# STM32-ROMI_Rev_A_4_3V_5V.net
KiCad netlist of a schematic drawn in Altium Designer
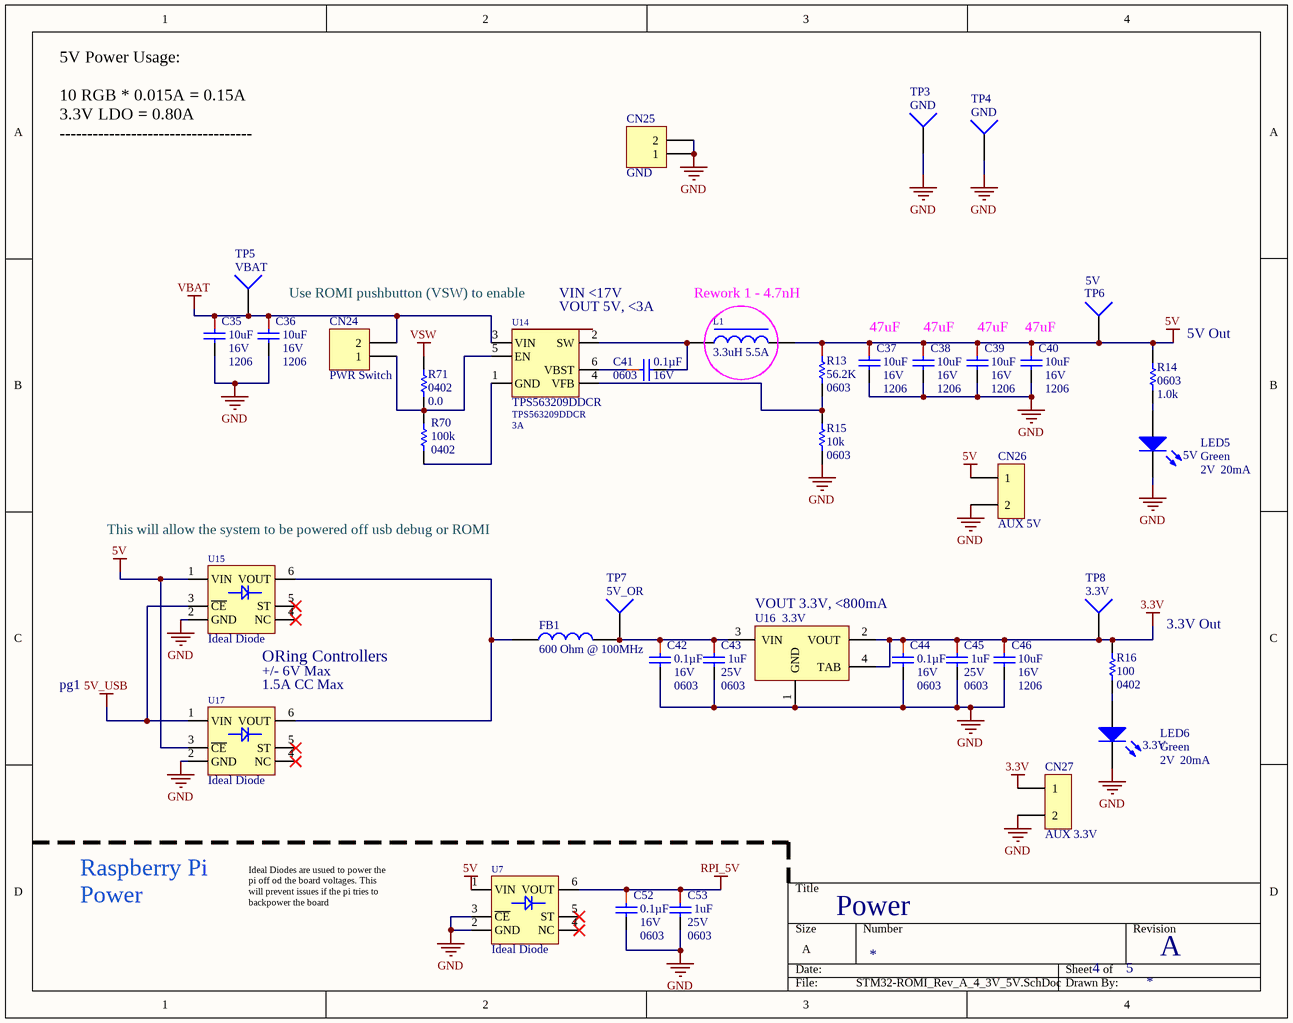
[diagram p0: STM32-ROMI_Rev_A_4_3V_5V.SchDoc]

(export (version "E")
  (design (tool "Eeschema 10.0.6"))
  (components
    (comp (ref "C35")
      (value "10uF")
      (footprint "CAPC1206(3216)_M")
      (fields (field (name "VOLTAGE - RATED") "16V") (field (name "PACKAGE") "1206"))
      (libsource (lib "Kyle-Passive") (part "CAP CER 10UF 16V 1206"))
    )
    (comp (ref "C36")
      (value "10uF")
      (footprint "CAPC1206(3216)_M")
      (fields (field (name "VOLTAGE - RATED") "16V") (field (name "PACKAGE") "1206"))
      (libsource (lib "Kyle-Passive") (part "CAP CER 10UF 16V 1206"))
    )
    (comp (ref "C37")
      (value "10uF")
      (footprint "CAPC1206(3216)_M")
      (fields (field (name "VOLTAGE - RATED") "16V") (field (name "PACKAGE") "1206"))
      (libsource (lib "Kyle-Passive") (part "CAP CER 10UF 16V 1206"))
    )
    (comp (ref "C38")
      (value "10uF")
      (footprint "CAPC1206(3216)_M")
      (fields (field (name "VOLTAGE - RATED") "16V") (field (name "PACKAGE") "1206"))
      (libsource (lib "Kyle-Passive") (part "CAP CER 10UF 16V 1206"))
    )
    (comp (ref "C39")
      (value "10uF")
      (footprint "CAPC1206(3216)_M")
      (fields (field (name "VOLTAGE - RATED") "16V") (field (name "PACKAGE") "1206"))
      (libsource (lib "Kyle-Passive") (part "CAP CER 10UF 16V 1206"))
    )
    (comp (ref "C40")
      (value "10uF")
      (footprint "CAPC1206(3216)_M")
      (fields (field (name "VOLTAGE - RATED") "16V") (field (name "PACKAGE") "1206"))
      (libsource (lib "Kyle-Passive") (part "CAP CER 10UF 16V 1206"))
    )
    (comp (ref "C41")
      (value "0.1uF")
      (footprint "CAPC0603(1608)_L")
      (description "0.1uF 0603 16V")
      (fields
        (field (name "MANUFACTURER") "Kemet")
        (field (name "MANUFACTURER PART NUMBER") "C0603C104K4RACTU")
        (field (name "CAPACITANCE") "0.1µF")
        (field (name "PACKAGE / CASE") "0603")
        (field (name "VOLTAGE - RATED") "16V")
      )
      (libsource (lib "Kyle-Passive") (part "CAP CER 0.1UF 16V 10% X7R 0603"))
    )
    (comp (ref "C42")
      (value "0.1uF")
      (footprint "CAPC0603(1608)_L")
      (description "0.1uF 0603 16V")
      (fields
        (field (name "MANUFACTURER") "Kemet")
        (field (name "MANUFACTURER PART NUMBER") "C0603C104K4RACTU")
        (field (name "CAPACITANCE") "0.1µF")
        (field (name "PACKAGE / CASE") "0603")
        (field (name "VOLTAGE - RATED") "16V")
      )
      (libsource (lib "Kyle-Passive") (part "CAP CER 0.1UF 16V 10% X7R 0603"))
    )
    (comp (ref "C43")
      (value "1uF")
      (footprint "CAPC0603(1608)_N")
      (description "1uF 0603 25V")
      (fields
        (field (name "MANUFACTURER") "TDK Corporation")
        (field (name "MANUFACTURER PART NUMBER") "CGA3E1X7R1E105K080AC")
        (field (name "VOLTAGE - RATED") "25V")
        (field (name "PACKAGE / CASE") "0603")
      )
      (libsource (lib "OLogic-Passive") (part "CAP CER 1UF 25V 10% X7R 0603"))
    )
    (comp (ref "C44")
      (value "0.1uF")
      (footprint "CAPC0603(1608)_L")
      (description "0.1uF 0603 16V")
      (fields
        (field (name "MANUFACTURER") "Kemet")
        (field (name "MANUFACTURER PART NUMBER") "C0603C104K4RACTU")
        (field (name "CAPACITANCE") "0.1µF")
        (field (name "PACKAGE / CASE") "0603")
        (field (name "VOLTAGE - RATED") "16V")
      )
      (libsource (lib "Kyle-Passive") (part "CAP CER 0.1UF 16V 10% X7R 0603"))
    )
    (comp (ref "C45")
      (value "1uF")
      (footprint "CAPC0603(1608)_N")
      (description "1uF 0603 25V")
      (fields
        (field (name "MANUFACTURER") "TDK Corporation")
        (field (name "MANUFACTURER PART NUMBER") "CGA3E1X7R1E105K080AC")
        (field (name "VOLTAGE - RATED") "25V")
        (field (name "PACKAGE / CASE") "0603")
      )
      (libsource (lib "OLogic-Passive") (part "CAP CER 1UF 25V 10% X7R 0603"))
    )
    (comp (ref "C46")
      (value "10uF")
      (footprint "CAPC1206(3216)_M")
      (fields (field (name "VOLTAGE - RATED") "16V") (field (name "PACKAGE") "1206"))
      (libsource (lib "Kyle-Passive") (part "CAP CER 10UF 16V 1206"))
    )
    (comp (ref "C52")
      (value "0.1uF")
      (footprint "CAPC0603(1608)_L")
      (description "0.1uF 0603 16V")
      (fields
        (field (name "MANUFACTURER") "Kemet")
        (field (name "MANUFACTURER PART NUMBER") "C0603C104K4RACTU")
        (field (name "CAPACITANCE") "0.1µF")
        (field (name "PACKAGE / CASE") "0603")
        (field (name "VOLTAGE - RATED") "16V")
      )
      (libsource (lib "Kyle-Passive") (part "CAP CER 0.1UF 16V 10% X7R 0603"))
    )
    (comp (ref "C53")
      (value "1uF")
      (footprint "CAPC0603(1608)_N")
      (description "1uF 0603 25V")
      (fields
        (field (name "MANUFACTURER") "TDK Corporation")
        (field (name "MANUFACTURER PART NUMBER") "CGA3E1X7R1E105K080AC")
        (field (name "VOLTAGE - RATED") "25V")
        (field (name "PACKAGE / CASE") "0603")
      )
      (libsource (lib "OLogic-Passive") (part "CAP CER 1UF 25V 10% X7R 0603"))
    )
    (comp (ref "CN24")
      (value "PWR Switch")
      (footprint "HDR1X2")
      (description "Header, 2-Pin")
      (fields
        (field (name "MANUFACTURER") "Sullins Connector Solutions")
        (field (name "MANUFACTURER PART NUMBER") "PRPC002SAAN-RC")
      )
      (libsource (lib "OLogic-Connectors") (part "Header 2"))
    )
    (comp (ref "CN25")
      (value "GND")
      (footprint "HDR1X2")
      (description "Header, 2-Pin")
      (fields
        (field (name "MANUFACTURER") "Sullins Connector Solutions")
        (field (name "MANUFACTURER PART NUMBER") "PRPC002SAAN-RC")
      )
      (libsource (lib "OLogic-Connectors") (part "Header 2"))
    )
    (comp (ref "CN26")
      (value "AUX 5V")
      (footprint "Molex 1x2 Microfit 3.0")
      (description "Molex Microfit 1x2 Vert Header")
      (fields
        (field (name "MANUFACTURER") "Molex, LLC")
        (field (name "MANUFACTURER PART NUMBER") "0430450227")
      )
      (libsource (lib "OLogic-Connectors") (part "MICROFIT 3.0 HDR VERT CPI 2CKT"))
    )
    (comp (ref "CN27")
      (value "AUX 3.3V")
      (footprint "Molex 1x2 Microfit 3.0")
      (description "Molex Microfit 1x2 Vert Header")
      (fields
        (field (name "MANUFACTURER") "Molex, LLC")
        (field (name "MANUFACTURER PART NUMBER") "0430450227")
      )
      (libsource (lib "OLogic-Connectors") (part "MICROFIT 3.0 HDR VERT CPI 2CKT"))
    )
    (comp (ref "FB1")
      (value "600 Ohm @ 100MHz")
      (footprint "RESC0805(2012)_N")
      (description "600 OHM 0805 2.0A")
      (fields
        (field (name "MANUFACTURER") "Wurth Electronics Inc")
        (field (name "MANUFACTURER PART NUMBER") "742792040")
        (field (name "CREATOR") "osman")
      )
      (libsource (lib "OLogic-Passive") (part "FERRITE 600 OHM 2.0A 0805"))
    )
    (comp (ref "L1")
      (value "3.3uH 5.5A")
      (footprint "YSPI0530-3R3M")
      (description "Power Inductors 3.3uH ±20% 5.5A SMD,5.2x4.7x3mm RoHS")
      (fields (field (name "MANUFACTURER PART") "YSPI0530-3R3M"))
      (libsource (lib "Kyle-Passive") (part "FIXED IND 3.3UH 5.5A 28 MOHM SMD"))
    )
    (comp (ref "LED5")
      (value "5V")
      (footprint "SM-LED-0603")
      (description "LED GREEN CLEAR THIN 0603 SMD")
      (fields
        (field (name "MANUFACTURER") "Lite-On Inc")
        (field (name "MANUFACTURER PART NUMBER") "LTST-C191KGKT")
        (field (name "COLOR") "Green")
        (field (name "VOLTAGE - FORWARD (VF) (TYP)") "2V")
        (field (name "CURRENT - TEST") "20mA")
      )
      (libsource (lib "Kyle-Diode-Opto-LED") (part "LTST-C191KGKT"))
    )
    (comp (ref "LED6")
      (value "3.3V")
      (footprint "SM-LED-0603")
      (description "LED GREEN CLEAR THIN 0603 SMD")
      (fields
        (field (name "MANUFACTURER") "Lite-On Inc")
        (field (name "MANUFACTURER PART NUMBER") "LTST-C191KGKT")
        (field (name "COLOR") "Green")
        (field (name "VOLTAGE - FORWARD (VF) (TYP)") "2V")
        (field (name "CURRENT - TEST") "20mA")
      )
      (libsource (lib "Kyle-Diode-Opto-LED") (part "LTST-C191KGKT"))
    )
    (comp (ref "R13")
      (value "56.2K")
      (footprint "RESC0603(1608)_L")
      (description "RES SMD 56.2K OHM 1% 1/10W 0603")
      (fields (field (name "PACKAGE / CASE") "0603"))
      (libsource (lib "Kyle-Passive") (part "RES SMD 56.2K OHM 1% 1/10W 0603"))
    )
    (comp (ref "R14")
      (value "1.0K")
      (footprint "RESC0603(1608)_N")
      (description "1.0K 0603")
      (fields
        (field (name "MANUFACTURER") "Stackpole Electronics Inc.")
        (field (name "MANUFACTURER PART NUMBER") "RMCF0603FT1K00")
        (field (name "PACKAGE / CASE") "0603")
        (field (name "RESISTANCE (OHMS)") "1.0k")
      )
      (libsource (lib "Kyle-Passive") (part "RES 1K OHM 1% 1/10W 0603"))
    )
    (comp (ref "R15")
      (value "10K 1%")
      (footprint "RESC0603(1608)_L")
      (description "10K 0603")
      (fields
        (field (name "MANUFACTURER") "Panasonic Electronic Components")
        (field (name "MANUFACTURER PART NUMBER") "ERJ-3EKF1002V")
        (field (name "RESISTANCE (OHMS)") "10k")
        (field (name "PACKAGE / CASE") "0603")
      )
      (libsource (lib "Kyle-Passive") (part "RES 10K OHM 1/10W 1% 0603 SMD"))
    )
    (comp (ref "R16")
      (value "100")
      (footprint "RESC0402(1005)_N")
      (description "100 0402")
      (fields
        (field (name "MANUFACTURER") "Yageo")
        (field (name "MANUFACTURER PART NUMBER") "RC0402FR-07100RL")
        (field (name "SUPPLIER DEVICE PACKAGE") "0402")
      )
      (libsource (lib "OLogic-Passive") (part "RES 100 OHM 1% 1/16W 0402"))
    )
    (comp (ref "R70")
      (value "100K 0402")
      (footprint "RESC0402(1005)_L")
      (fields
        (field (name "MANUFACTURER") "Yageo")
        (field (name "MANUFACTURER PART NUMBER") "RC0402FR-07100KL")
        (field (name "TOLERANCE") "±1%")
        (field (name "SUPPLIER DEVICE PACKAGE") "0402")
        (field (name "RESISTANCE (OHMS)") "100k")
      )
      (libsource (lib "OLogic-Passive") (part "RES 100K OHM 1% 1/16W 0402"))
    )
    (comp (ref "R71")
      (value "0")
      (footprint "RESC0402(1005)_L")
      (description "0.0 0402")
      (fields
        (field (name "MANUFACTURER") "Panasonic Electronic Components")
        (field (name "MANUFACTURER PART NUMBER") "ERJ-2GE0R00X")
        (field (name "SUPPLIER DEVICE PACKAGE") "0402")
        (field (name "RESISTANCE (OHMS)") "0.0")
        (field (name "CREATOR") "osman")
      )
      (libsource (lib "OLogic-Passive") (part "RES 0.0 OHM JUMPER 1/10W 0402"))
    )
    (comp (ref "TP3")
      (value "GND")
      (footprint "TestPoint-SM")
      (description "Test Point")
      (libsource (lib "OLogic-Misc") (part "TestPoint"))
    )
    (comp (ref "TP4")
      (value "GND")
      (footprint "TestPoint-SM")
      (description "Test Point")
      (libsource (lib "OLogic-Misc") (part "TestPoint"))
    )
    (comp (ref "TP5")
      (value "VBAT")
      (footprint "TestPoint-SM")
      (description "Test Point")
      (libsource (lib "OLogic-Misc") (part "TestPoint"))
    )
    (comp (ref "TP6")
      (value "5V")
      (footprint "TestPoint-SM")
      (description "Test Point")
      (libsource (lib "OLogic-Misc") (part "TestPoint"))
    )
    (comp (ref "TP7")
      (value "5V_OR")
      (footprint "TestPoint-SM")
      (description "Test Point")
      (libsource (lib "OLogic-Misc") (part "TestPoint"))
    )
    (comp (ref "TP8")
      (value "3.3V")
      (footprint "TestPoint-SM")
      (description "Test Point")
      (libsource (lib "OLogic-Misc") (part "TestPoint"))
    )
    (comp (ref "U7")
      (value "Ideal Diode")
      (footprint "SC-70-6")
      (description "OR Controller P-Channel 1.5A CC")
      (libsource (lib "Kyle-Reg-Convert") (part "LM66100DCKT"))
    )
    (comp (ref "U14")
      (value "TPS563209DDCR")
      (footprint "SOT23-6")
      (description "IC REG BUCK ADJ 3A TSOT23-6")
      (fields
        (field (name "MANUFACTURER PART NUMBER") "TPS563209DDCR")
        (field (name "CURRENT - OUTPUT") "3A")
      )
      (libsource (lib "Kyle-Reg-Convert") (part "TPS563209DDCR"))
    )
    (comp (ref "U15")
      (value "Ideal Diode")
      (footprint "SC-70-6")
      (description "OR Controller P-Channel 1.5A CC")
      (libsource (lib "Kyle-Reg-Convert") (part "LM66100DCKT"))
    )
    (comp (ref "U16")
      (value "3.3V")
      (footprint "DSO-G3")
      (description "3.3 volt fixed regulator, 800mA")
      (libsource (lib "OLogic-Reg-Convert") (part "LD1117S33"))
    )
    (comp (ref "U17")
      (value "Ideal Diode")
      (footprint "SC-70-6")
      (description "OR Controller P-Channel 1.5A CC")
      (libsource (lib "Kyle-Reg-Convert") (part "LM66100DCKT"))
    )
  )
  (nets
    (net (code "1") (name "3.3V") (class "Default")
      (node (ref "C44") (pin "1") (pinfunction "1_1") (pintype "passive"))
      (node (ref "C45") (pin "1") (pinfunction "1_1") (pintype "passive"))
      (node (ref "C46") (pin "1") (pinfunction "1_1") (pintype "passive"))
      (node (ref "CN27") (pin "1") (pinfunction "1_1") (pintype "passive"))
      (node (ref "R16") (pin "2") (pinfunction "2_2") (pintype "passive"))
      (node (ref "TP8") (pin "1") (pinfunction "1_1") (pintype "passive"))
      (node (ref "U16") (pin "2") (pinfunction "VOUT_2") (pintype "power_in"))
      (node (ref "U16") (pin "4") (pinfunction "TAB_4") (pintype "power_in"))
    )
    (net (code "2") (name "5V") (class "Default")
      (node (ref "C37") (pin "1") (pinfunction "1_1") (pintype "passive"))
      (node (ref "C38") (pin "1") (pinfunction "1_1") (pintype "passive"))
      (node (ref "C39") (pin "1") (pinfunction "1_1") (pintype "passive"))
      (node (ref "C40") (pin "1") (pinfunction "1_1") (pintype "passive"))
      (node (ref "CN26") (pin "1") (pinfunction "1_1") (pintype "passive"))
      (node (ref "L1") (pin "2") (pinfunction "2_2") (pintype "passive"))
      (node (ref "R13") (pin "1") (pinfunction "1_1") (pintype "passive"))
      (node (ref "R14") (pin "2") (pinfunction "2_2") (pintype "passive"))
      (node (ref "TP6") (pin "1") (pinfunction "1_1") (pintype "passive"))
      (node (ref "U15") (pin "1") (pinfunction "VIN_1") (pintype "passive"))
      (node (ref "U17") (pin "3") (pinfunction "~{CE}_3") (pintype "passive"))
      (node (ref "U7") (pin "1") (pinfunction "VIN_1") (pintype "passive"))
    )
    (net (code "3") (name "5V_USB") (class "Default")
      (node (ref "U15") (pin "3") (pinfunction "~{CE}_3") (pintype "passive"))
      (node (ref "U17") (pin "1") (pinfunction "VIN_1") (pintype "passive"))
    )
    (net (code "4") (name "GND") (class "Default")
      (node (ref "C35") (pin "2") (pinfunction "2_2") (pintype "passive"))
      (node (ref "C36") (pin "2") (pinfunction "2_2") (pintype "passive"))
      (node (ref "C37") (pin "2") (pinfunction "2_2") (pintype "passive"))
      (node (ref "C38") (pin "2") (pinfunction "2_2") (pintype "passive"))
      (node (ref "C39") (pin "2") (pinfunction "2_2") (pintype "passive"))
      (node (ref "C40") (pin "2") (pinfunction "2_2") (pintype "passive"))
      (node (ref "C42") (pin "2") (pinfunction "2_2") (pintype "passive"))
      (node (ref "C43") (pin "2") (pinfunction "2_2") (pintype "passive"))
      (node (ref "C44") (pin "2") (pinfunction "2_2") (pintype "passive"))
      (node (ref "C45") (pin "2") (pinfunction "2_2") (pintype "passive"))
      (node (ref "C46") (pin "2") (pinfunction "2_2") (pintype "passive"))
      (node (ref "C52") (pin "2") (pinfunction "2_2") (pintype "passive"))
      (node (ref "C53") (pin "2") (pinfunction "2_2") (pintype "passive"))
      (node (ref "CN25") (pin "1") (pinfunction "1_1") (pintype "passive"))
      (node (ref "CN25") (pin "2") (pinfunction "2_2") (pintype "passive"))
      (node (ref "CN26") (pin "2") (pinfunction "2_2") (pintype "passive"))
      (node (ref "CN27") (pin "2") (pinfunction "2_2") (pintype "passive"))
      (node (ref "LED5") (pin "2") (pinfunction "2_2") (pintype "passive"))
      (node (ref "LED6") (pin "2") (pinfunction "2_2") (pintype "passive"))
      (node (ref "R15") (pin "1") (pinfunction "1_1") (pintype "passive"))
      (node (ref "TP3") (pin "1") (pinfunction "1_1") (pintype "passive"))
      (node (ref "TP4") (pin "1") (pinfunction "1_1") (pintype "passive"))
      (node (ref "U15") (pin "2") (pinfunction "GND_2") (pintype "passive"))
      (node (ref "U16") (pin "1") (pinfunction "GND_1") (pintype "power_in"))
      (node (ref "U17") (pin "2") (pinfunction "GND_2") (pintype "passive"))
      (node (ref "U7") (pin "2") (pinfunction "GND_2") (pintype "passive"))
      (node (ref "U7") (pin "3") (pinfunction "~{CE}_3") (pintype "passive"))
    )
    (net (code "5") (name "Net-(LED5-Pad1)") (class "Default")
      (node (ref "LED5") (pin "1") (pinfunction "1_1") (pintype "passive"))
      (node (ref "R14") (pin "1") (pinfunction "1_1") (pintype "passive"))
    )
    (net (code "6") (name "Net-(LED6-Pad1)") (class "Default")
      (node (ref "LED6") (pin "1") (pinfunction "1_1") (pintype "passive"))
      (node (ref "R16") (pin "1") (pinfunction "1_1") (pintype "passive"))
    )
    (net (code "7") (name "Net-(U14-EN)") (class "Default")
      (node (ref "CN24") (pin "1") (pinfunction "1_1") (pintype "passive"))
      (node (ref "R70") (pin "2") (pinfunction "2_2") (pintype "passive"))
      (node (ref "R71") (pin "2") (pinfunction "2_2") (pintype "passive"))
      (node (ref "U14") (pin "5") (pinfunction "EN_5") (pintype "power_in"))
    )
    (net (code "8") (name "Net-(U14-GND)") (class "Default")
      (node (ref "R70") (pin "1") (pinfunction "1_1") (pintype "passive"))
      (node (ref "U14") (pin "1") (pinfunction "GND_1") (pintype "power_in"))
    )
    (net (code "9") (name "Net-(U14-SW)") (class "Default")
      (node (ref "C41") (pin "2") (pinfunction "2_2") (pintype "passive"))
      (node (ref "L1") (pin "1") (pinfunction "1_1") (pintype "passive"))
      (node (ref "U14") (pin "2") (pinfunction "SW_2") (pintype "power_in"))
    )
    (net (code "10") (name "Net-(U14-VBST)") (class "Default")
      (node (ref "C41") (pin "1") (pinfunction "1_1") (pintype "passive"))
      (node (ref "U14") (pin "6") (pinfunction "VBST_6") (pintype "power_in"))
    )
    (net (code "11") (name "Net-(U14-VFB)") (class "Default")
      (node (ref "R13") (pin "2") (pinfunction "2_2") (pintype "passive"))
      (node (ref "R15") (pin "2") (pinfunction "2_2") (pintype "passive"))
      (node (ref "U14") (pin "4") (pinfunction "VFB_4") (pintype "power_in"))
    )
    (net (code "12") (name "Net-(U15-VOUT)") (class "Default")
      (node (ref "FB1") (pin "1") (pinfunction "1_1") (pintype "passive"))
      (node (ref "U15") (pin "6") (pinfunction "VOUT_6") (pintype "passive"))
      (node (ref "U17") (pin "6") (pinfunction "VOUT_6") (pintype "passive"))
    )
    (net (code "13") (name "Net-(U16-VIN)") (class "Default")
      (node (ref "C42") (pin "1") (pinfunction "1_1") (pintype "passive"))
      (node (ref "C43") (pin "1") (pinfunction "1_1") (pintype "passive"))
      (node (ref "FB1") (pin "2") (pinfunction "2_2") (pintype "passive"))
      (node (ref "TP7") (pin "1") (pinfunction "1_1") (pintype "passive"))
      (node (ref "U16") (pin "3") (pinfunction "VIN_3") (pintype "power_in"))
    )
    (net (code "14") (name "RPI_5V") (class "Default")
      (node (ref "C52") (pin "1") (pinfunction "1_1") (pintype "passive"))
      (node (ref "C53") (pin "1") (pinfunction "1_1") (pintype "passive"))
      (node (ref "U7") (pin "6") (pinfunction "VOUT_6") (pintype "passive"))
    )
    (net (code "15") (name "VBAT") (class "Default")
      (node (ref "C35") (pin "1") (pinfunction "1_1") (pintype "passive"))
      (node (ref "C36") (pin "1") (pinfunction "1_1") (pintype "passive"))
      (node (ref "CN24") (pin "2") (pinfunction "2_2") (pintype "passive"))
      (node (ref "TP5") (pin "1") (pinfunction "1_1") (pintype "passive"))
      (node (ref "U14") (pin "3") (pinfunction "VIN_3") (pintype "power_in"))
    )
    (net (code "16") (name "VSW") (class "Default")
      (node (ref "R71") (pin "1") (pinfunction "1_1") (pintype "passive"))
    )
    (net (code "17") (name "unconnected-(U7-NC-Pad4)") (class "Default")
      (node (ref "U7") (pin "4") (pinfunction "NC_4") (pintype "passive+no_connect"))
    )
    (net (code "18") (name "unconnected-(U7-ST-Pad5)") (class "Default")
      (node (ref "U7") (pin "5") (pinfunction "ST_5") (pintype "passive+no_connect"))
    )
    (net (code "19") (name "unconnected-(U15-NC-Pad4)") (class "Default")
      (node (ref "U15") (pin "4") (pinfunction "NC_4") (pintype "passive+no_connect"))
    )
    (net (code "20") (name "unconnected-(U15-ST-Pad5)") (class "Default")
      (node (ref "U15") (pin "5") (pinfunction "ST_5") (pintype "passive+no_connect"))
    )
    (net (code "21") (name "unconnected-(U17-NC-Pad4)") (class "Default")
      (node (ref "U17") (pin "4") (pinfunction "NC_4") (pintype "passive+no_connect"))
    )
    (net (code "22") (name "unconnected-(U17-ST-Pad5)") (class "Default")
      (node (ref "U17") (pin "5") (pinfunction "ST_5") (pintype "passive+no_connect"))
    )
  )
)
